# od1_redraw.net
KiCad netlist of a schematic drawn in EAGLE
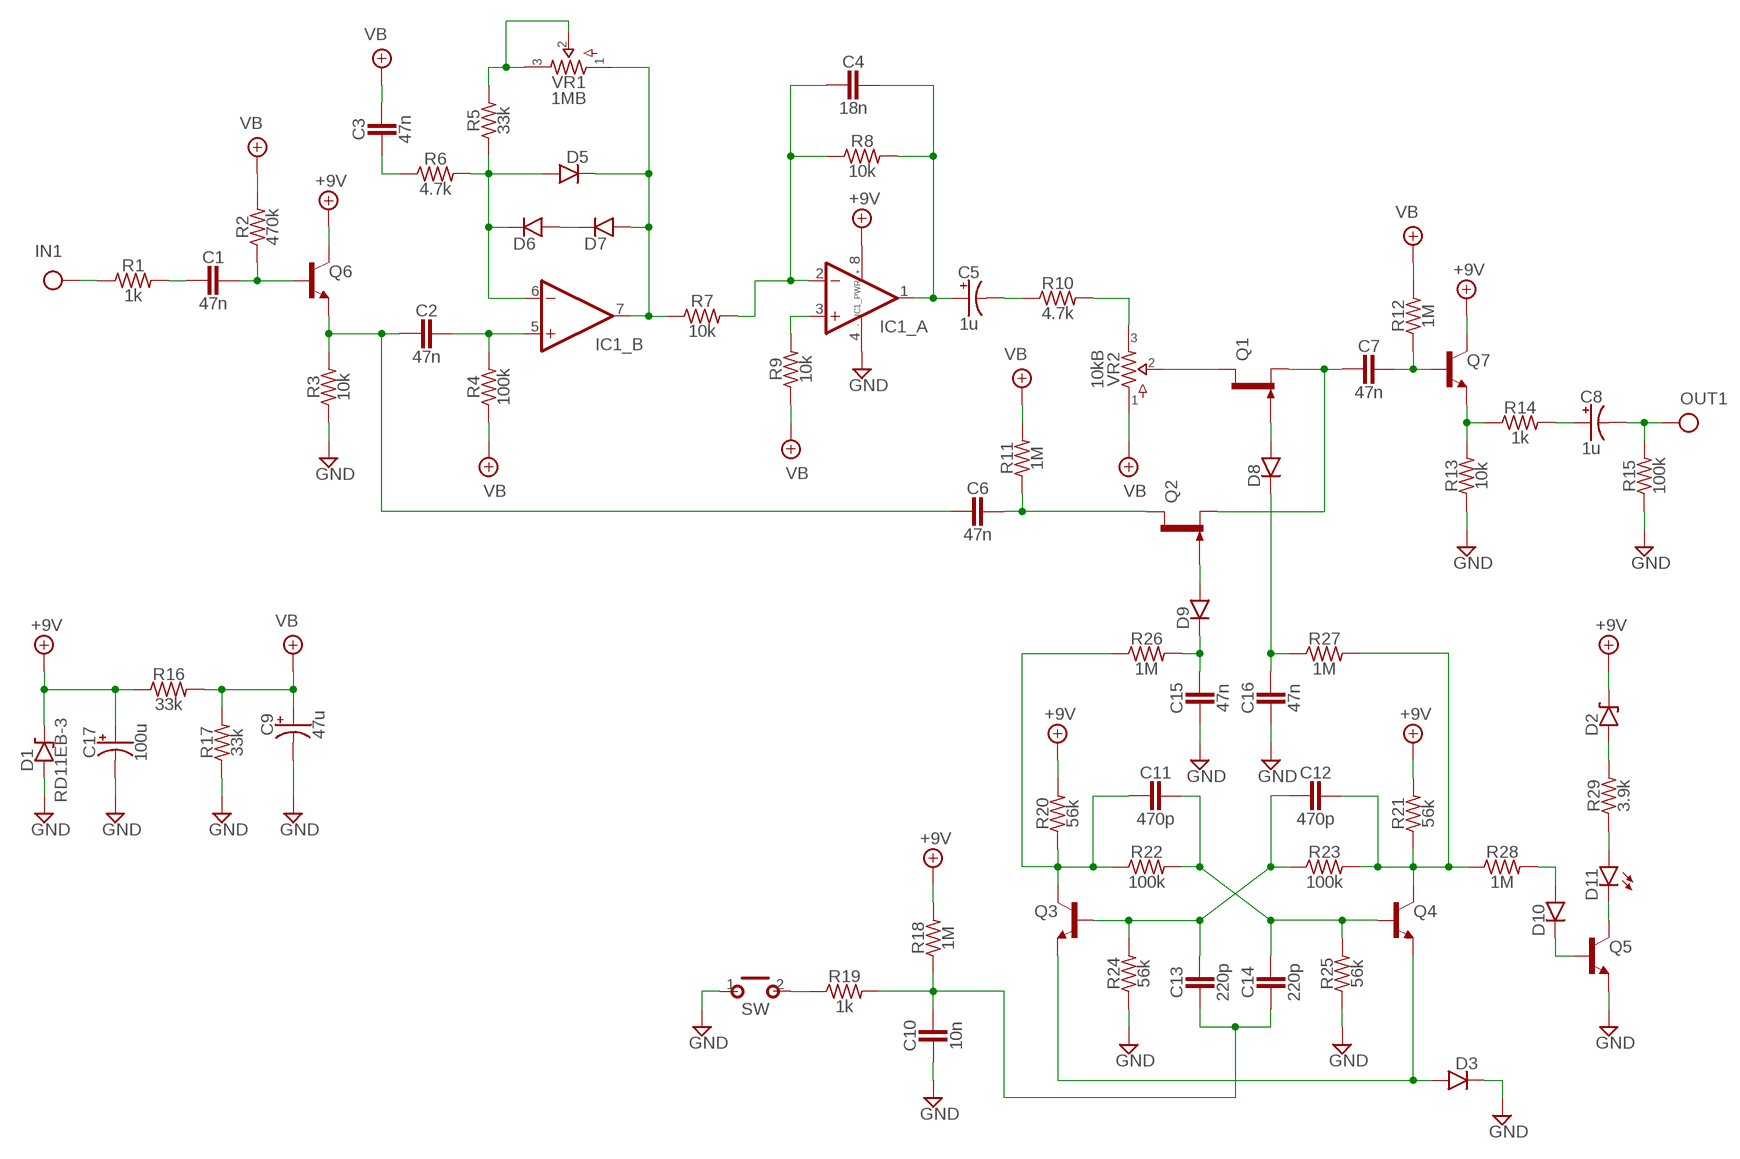
[diagram p0: schematic, sheet 1]

(export (version "E")
  (design (tool "Eeschema 10.0.6"))
  (components
    (comp (ref "C1")
      (value "47n")
      (footprint "eagle-import:BOX_SMALL")
      (libsource (lib "eagle-import") (part "CER/FILMBOX.1"))
    )
    (comp (ref "C2")
      (value "47n")
      (footprint "eagle-import:BOX_SMALL")
      (libsource (lib "eagle-import") (part "CER/FILMBOX.1"))
    )
    (comp (ref "C3")
      (value "47n")
      (footprint "eagle-import:BOX_SMALL")
      (libsource (lib "eagle-import") (part "CER/FILMBOX.1"))
    )
    (comp (ref "C4")
      (value "18n")
      (footprint "eagle-import:BOX_SMALL")
      (libsource (lib "eagle-import") (part "CER/FILMBOX.1"))
    )
    (comp (ref "C5")
      (value "1u")
      (footprint "eagle-import:040_020")
      (libsource (lib "eagle-import") (part "0400"))
    )
    (comp (ref "C6")
      (value "47n")
      (footprint "eagle-import:BOX_SMALL")
      (libsource (lib "eagle-import") (part "CER/FILMBOX.1"))
    )
    (comp (ref "C7")
      (value "47n")
      (footprint "eagle-import:BOX_SMALL")
      (libsource (lib "eagle-import") (part "CER/FILMBOX.1"))
    )
    (comp (ref "C8")
      (value "1u")
      (footprint "eagle-import:040_020")
      (libsource (lib "eagle-import") (part "0400"))
    )
    (comp (ref "C9")
      (value "47u")
      (footprint "eagle-import:040_020")
      (libsource (lib "eagle-import") (part "0400"))
    )
    (comp (ref "C10")
      (value "10n")
      (footprint "eagle-import:BOX_SMALL")
      (libsource (lib "eagle-import") (part "CER/FILMBOX.1"))
    )
    (comp (ref "C11")
      (value "470p")
      (footprint "eagle-import:BOX_SMALL")
      (libsource (lib "eagle-import") (part "CER/FILMBOX.1"))
    )
    (comp (ref "C12")
      (value "470p")
      (footprint "eagle-import:BOX_SMALL")
      (libsource (lib "eagle-import") (part "CER/FILMBOX.1"))
    )
    (comp (ref "C13")
      (value "220p")
      (footprint "eagle-import:BOX_SMALL")
      (libsource (lib "eagle-import") (part "CER/FILMBOX.1"))
    )
    (comp (ref "C14")
      (value "220p")
      (footprint "eagle-import:BOX_SMALL")
      (libsource (lib "eagle-import") (part "CER/FILMBOX.1"))
    )
    (comp (ref "C15")
      (value "47n")
      (footprint "eagle-import:BOX_SMALL")
      (libsource (lib "eagle-import") (part "CER/FILMBOX.1"))
    )
    (comp (ref "C16")
      (value "47n")
      (footprint "eagle-import:BOX_SMALL")
      (libsource (lib "eagle-import") (part "CER/FILMBOX.1"))
    )
    (comp (ref "C17")
      (value "100u")
      (footprint "eagle-import:040_020")
      (libsource (lib "eagle-import") (part "0400"))
    )
    (comp (ref "D1")
      (value "RD11EB-3")
      (footprint "eagle-import:DO41-2")
      (libsource (lib "eagle-import") (part "ZENER.2"))
    )
    (comp (ref "D2")
      (value "ZENER.2")
      (footprint "eagle-import:DO41-2")
      (libsource (lib "eagle-import") (part "ZENER.2"))
    )
    (comp (ref "D3")
      (value "DO35.2")
      (footprint "eagle-import:DO35-2")
      (libsource (lib "eagle-import") (part "DO35.2"))
    )
    (comp (ref "D5")
      (value "DO35.2")
      (footprint "eagle-import:DO35-2")
      (libsource (lib "eagle-import") (part "DO35.2"))
    )
    (comp (ref "D6")
      (value "DO35.2")
      (footprint "eagle-import:DO35-2")
      (libsource (lib "eagle-import") (part "DO35.2"))
    )
    (comp (ref "D7")
      (value "DO35.2")
      (footprint "eagle-import:DO35-2")
      (libsource (lib "eagle-import") (part "DO35.2"))
    )
    (comp (ref "D8")
      (value "DO35.2")
      (footprint "eagle-import:DO35-2")
      (libsource (lib "eagle-import") (part "DO35.2"))
    )
    (comp (ref "D9")
      (value "DO35.2")
      (footprint "eagle-import:DO35-2")
      (libsource (lib "eagle-import") (part "DO35.2"))
    )
    (comp (ref "D10")
      (value "DO35.2")
      (footprint "eagle-import:DO35-2")
      (libsource (lib "eagle-import") (part "DO35.2"))
    )
    (comp (ref "D11")
      (value "SLP1358")
      (footprint "eagle-import:3MM_D")
      (libsource (lib "eagle-import") (part "LED"))
    )
    (comp (ref "IC1")
      (value "DUALTH")
      (footprint "eagle-import:DIL0")
      (libsource (lib "eagle-import") (part "DUALTH"))
    )
    (comp (ref "Q1")
      (value "2N5457")
      (footprint "eagle-import:TO92-")
      (libsource (lib "eagle-import") (part "2N5457"))
    )
    (comp (ref "Q2")
      (value "2N5457")
      (footprint "eagle-import:TO92-")
      (libsource (lib "eagle-import") (part "2N5457"))
    )
    (comp (ref "Q3")
      (value "2SC828A")
      (footprint "eagle-import:TO92-")
      (libsource (lib "eagle-import") (part "2SC828A"))
    )
    (comp (ref "Q4")
      (value "2SC828A")
      (footprint "eagle-import:TO92-")
      (libsource (lib "eagle-import") (part "2SC828A"))
    )
    (comp (ref "Q5")
      (value "2SC828A")
      (footprint "eagle-import:TO92-")
      (libsource (lib "eagle-import") (part "2SC828A"))
    )
    (comp (ref "Q6")
      (value "2SC828A")
      (footprint "eagle-import:TO92-")
      (libsource (lib "eagle-import") (part "2SC828A"))
    )
    (comp (ref "Q7")
      (value "2SC828A")
      (footprint "eagle-import:TO92-")
      (libsource (lib "eagle-import") (part "2SC828A"))
    )
    (comp (ref "R1")
      (value "1k")
      (footprint "eagle-import:R0207_3")
      (libsource (lib "eagle-import") (part "R_.3B"))
    )
    (comp (ref "R2")
      (value "470k")
      (footprint "eagle-import:R0207_3")
      (libsource (lib "eagle-import") (part "R_.3B"))
    )
    (comp (ref "R3")
      (value "10k")
      (footprint "eagle-import:R0207_3")
      (libsource (lib "eagle-import") (part "R_.3B"))
    )
    (comp (ref "R4")
      (value "100k")
      (footprint "eagle-import:R0207_3")
      (libsource (lib "eagle-import") (part "R_.3B"))
    )
    (comp (ref "R5")
      (value "33k")
      (footprint "eagle-import:R0207_3")
      (libsource (lib "eagle-import") (part "R_.3B"))
    )
    (comp (ref "R6")
      (value "4.7k")
      (footprint "eagle-import:R0207_3")
      (libsource (lib "eagle-import") (part "R_.3B"))
    )
    (comp (ref "R7")
      (value "10k")
      (footprint "eagle-import:R0207_3")
      (libsource (lib "eagle-import") (part "R_.3B"))
    )
    (comp (ref "R8")
      (value "10k")
      (footprint "eagle-import:R0207_3")
      (libsource (lib "eagle-import") (part "R_.3B"))
    )
    (comp (ref "R9")
      (value "10k")
      (footprint "eagle-import:R0207_3")
      (libsource (lib "eagle-import") (part "R_.3B"))
    )
    (comp (ref "R10")
      (value "4.7k")
      (footprint "eagle-import:R0207_3")
      (libsource (lib "eagle-import") (part "R_.3B"))
    )
    (comp (ref "R11")
      (value "1M")
      (footprint "eagle-import:R0207_3")
      (libsource (lib "eagle-import") (part "R_.3B"))
    )
    (comp (ref "R12")
      (value "1M")
      (footprint "eagle-import:R0207_3")
      (libsource (lib "eagle-import") (part "R_.3B"))
    )
    (comp (ref "R13")
      (value "10k")
      (footprint "eagle-import:R0207_3")
      (libsource (lib "eagle-import") (part "R_.3B"))
    )
    (comp (ref "R14")
      (value "1k")
      (footprint "eagle-import:R0207_3")
      (libsource (lib "eagle-import") (part "R_.3B"))
    )
    (comp (ref "R15")
      (value "100k")
      (footprint "eagle-import:R0207_3")
      (libsource (lib "eagle-import") (part "R_.3B"))
    )
    (comp (ref "R16")
      (value "33k")
      (footprint "eagle-import:R0207_3")
      (libsource (lib "eagle-import") (part "R_.3B"))
    )
    (comp (ref "R17")
      (value "33k")
      (footprint "eagle-import:R0207_3")
      (libsource (lib "eagle-import") (part "R_.3B"))
    )
    (comp (ref "R18")
      (value "1M")
      (footprint "eagle-import:R0207_3")
      (libsource (lib "eagle-import") (part "R_.3B"))
    )
    (comp (ref "R19")
      (value "1k")
      (footprint "eagle-import:R0207_3")
      (libsource (lib "eagle-import") (part "R_.3B"))
    )
    (comp (ref "R20")
      (value "56k")
      (footprint "eagle-import:R0207_3")
      (libsource (lib "eagle-import") (part "R_.3B"))
    )
    (comp (ref "R21")
      (value "56k")
      (footprint "eagle-import:R0207_3")
      (libsource (lib "eagle-import") (part "R_.3B"))
    )
    (comp (ref "R22")
      (value "100k")
      (footprint "eagle-import:R0207_3")
      (libsource (lib "eagle-import") (part "R_.3B"))
    )
    (comp (ref "R23")
      (value "100k")
      (footprint "eagle-import:R0207_3")
      (libsource (lib "eagle-import") (part "R_.3B"))
    )
    (comp (ref "R24")
      (value "56k")
      (footprint "eagle-import:R0207_3")
      (libsource (lib "eagle-import") (part "R_.3B"))
    )
    (comp (ref "R25")
      (value "56k")
      (footprint "eagle-import:R0207_3")
      (libsource (lib "eagle-import") (part "R_.3B"))
    )
    (comp (ref "R26")
      (value "1M")
      (footprint "eagle-import:R0207_3")
      (libsource (lib "eagle-import") (part "R_.3B"))
    )
    (comp (ref "R27")
      (value "1M")
      (footprint "eagle-import:R0207_3")
      (libsource (lib "eagle-import") (part "R_.3B"))
    )
    (comp (ref "R28")
      (value "1M")
      (footprint "eagle-import:R0207_3")
      (libsource (lib "eagle-import") (part "R_.3B"))
    )
    (comp (ref "R29")
      (value "3.9k")
      (footprint "eagle-import:R0207_3")
      (libsource (lib "eagle-import") (part "R_.3B"))
    )
    (comp (ref "SW")
      (value "MOMENTARY")
      (footprint "eagle-import:SPST")
      (libsource (lib "eagle-import") (part "MOMENTARY"))
    )
    (comp (ref "VR1")
      (value "1MB")
      (footprint "eagle-import:16MM")
      (libsource (lib "eagle-import") (part "POTS16MM"))
    )
    (comp (ref "VR2")
      (value "10kB")
      (footprint "eagle-import:16MM")
      (libsource (lib "eagle-import") (part "POTS16MM"))
    )
  )
  (nets
    (net (code "1") (name "+9V") (class "Default")
      (node (ref "C17") (pin "+") (pinfunction "+_+") (pintype "passive"))
      (node (ref "D1") (pin "C") (pinfunction "C_C") (pintype "passive"))
      (node (ref "D2") (pin "C") (pinfunction "C_C") (pintype "passive"))
      (node (ref "IC1") (pin "8") (pinfunction "V+_8") (pintype "power_in"))
      (node (ref "Q6") (pin "2") (pinfunction "C_2") (pintype "passive"))
      (node (ref "Q7") (pin "2") (pinfunction "C_2") (pintype "passive"))
      (node (ref "R16") (pin "1") (pinfunction "1_1") (pintype "passive"))
      (node (ref "R18") (pin "2") (pinfunction "2_2") (pintype "passive"))
      (node (ref "R20") (pin "2") (pinfunction "2_2") (pintype "passive"))
      (node (ref "R21") (pin "2") (pinfunction "2_2") (pintype "passive"))
    )
    (net (code "2") (name "GND") (class "Default")
      (node (ref "C10") (pin "2") (pinfunction "2_2") (pintype "passive"))
      (node (ref "C15") (pin "2") (pinfunction "2_2") (pintype "passive"))
      (node (ref "C16") (pin "2") (pinfunction "2_2") (pintype "passive"))
      (node (ref "C17") (pin "-") (pinfunction "-_-") (pintype "passive"))
      (node (ref "C9") (pin "-") (pinfunction "-_-") (pintype "passive"))
      (node (ref "D1") (pin "A") (pinfunction "A_A") (pintype "passive"))
      (node (ref "D3") (pin "C") (pinfunction "C_C") (pintype "passive"))
      (node (ref "IC1") (pin "4") (pinfunction "V-_4") (pintype "power_in"))
      (node (ref "Q5") (pin "3") (pinfunction "E_3") (pintype "passive"))
      (node (ref "R13") (pin "1") (pinfunction "1_1") (pintype "passive"))
      (node (ref "R15") (pin "1") (pinfunction "1_1") (pintype "passive"))
      (node (ref "R17") (pin "1") (pinfunction "1_1") (pintype "passive"))
      (node (ref "R24") (pin "1") (pinfunction "1_1") (pintype "passive"))
      (node (ref "R25") (pin "1") (pinfunction "1_1") (pintype "passive"))
      (node (ref "R3") (pin "1") (pinfunction "1_1") (pintype "passive"))
      (node (ref "SW") (pin "1") (pinfunction "P_1") (pintype "passive"))
    )
    (net (code "3") (name "IN") (class "Default")
      (node (ref "R1") (pin "1") (pinfunction "1_1") (pintype "passive"))
    )
    (net (code "4") (name "Net-(C1-Pad2)") (class "Default")
      (node (ref "C1") (pin "2") (pinfunction "2_2") (pintype "passive"))
      (node (ref "R1") (pin "2") (pinfunction "2_2") (pintype "passive"))
    )
    (net (code "5") (name "Net-(C3-Pad2)") (class "Default")
      (node (ref "C3") (pin "2") (pinfunction "2_2") (pintype "passive"))
      (node (ref "R6") (pin "1") (pinfunction "1_1") (pintype "passive"))
    )
    (net (code "6") (name "Net-(C5-Pad-)") (class "Default")
      (node (ref "C5") (pin "-") (pinfunction "-_-") (pintype "passive"))
      (node (ref "R10") (pin "1") (pinfunction "1_1") (pintype "passive"))
    )
    (net (code "7") (name "Net-(C8-Pad+)") (class "Default")
      (node (ref "C8") (pin "+") (pinfunction "+_+") (pintype "passive"))
      (node (ref "R14") (pin "2") (pinfunction "2_2") (pintype "passive"))
    )
    (net (code "8") (name "Net-(C10-Pad1)") (class "Default")
      (node (ref "C10") (pin "1") (pinfunction "1_1") (pintype "passive"))
      (node (ref "C13") (pin "2") (pinfunction "2_2") (pintype "passive"))
      (node (ref "C14") (pin "2") (pinfunction "2_2") (pintype "passive"))
      (node (ref "R18") (pin "1") (pinfunction "1_1") (pintype "passive"))
      (node (ref "R19") (pin "2") (pinfunction "2_2") (pintype "passive"))
    )
    (net (code "9") (name "Net-(C15-Pad1)") (class "Default")
      (node (ref "C15") (pin "1") (pinfunction "1_1") (pintype "passive"))
      (node (ref "D9") (pin "C") (pinfunction "C_C") (pintype "passive"))
      (node (ref "R26") (pin "2") (pinfunction "2_2") (pintype "passive"))
    )
    (net (code "10") (name "Net-(C16-Pad1)") (class "Default")
      (node (ref "C16") (pin "1") (pinfunction "1_1") (pintype "passive"))
      (node (ref "D8") (pin "C") (pinfunction "C_C") (pintype "passive"))
      (node (ref "R27") (pin "1") (pinfunction "1_1") (pintype "passive"))
    )
    (net (code "11") (name "Net-(D2-PadA)") (class "Default")
      (node (ref "D2") (pin "A") (pinfunction "A_A") (pintype "passive"))
      (node (ref "R29") (pin "2") (pinfunction "2_2") (pintype "passive"))
    )
    (net (code "12") (name "Net-(D6-PadA)") (class "Default")
      (node (ref "D6") (pin "A") (pinfunction "A_A") (pintype "passive"))
      (node (ref "D7") (pin "C") (pinfunction "C_C") (pintype "passive"))
    )
    (net (code "13") (name "Net-(D10-PadA)") (class "Default")
      (node (ref "D10") (pin "A") (pinfunction "A_A") (pintype "passive"))
      (node (ref "R28") (pin "2") (pinfunction "2_2") (pintype "passive"))
    )
    (net (code "14") (name "Net-(D11-A)") (class "Default")
      (node (ref "D11") (pin "ANODE") (pinfunction "A_ANODE") (pintype "passive"))
      (node (ref "R29") (pin "1") (pinfunction "1_1") (pintype "passive"))
    )
    (net (code "15") (name "Net-(D11-C)") (class "Default")
      (node (ref "D11") (pin "P$1") (pinfunction "C_P$1") (pintype "passive"))
      (node (ref "Q5") (pin "2") (pinfunction "C_2") (pintype "passive"))
    )
    (net (code "16") (name "Net-(IC1A-+IN)") (class "Default")
      (node (ref "IC1") (pin "3") (pinfunction "+IN_3") (pintype "input"))
      (node (ref "R9") (pin "2") (pinfunction "2_2") (pintype "passive"))
    )
    (net (code "17") (name "Net-(IC1A--IN)") (class "Default")
      (node (ref "C4") (pin "2") (pinfunction "2_2") (pintype "passive"))
      (node (ref "IC1") (pin "2") (pinfunction "-IN_2") (pintype "input"))
      (node (ref "R7") (pin "2") (pinfunction "2_2") (pintype "passive"))
      (node (ref "R8") (pin "1") (pinfunction "1_1") (pintype "passive"))
    )
    (net (code "18") (name "Net-(IC1A-OUT)") (class "Default")
      (node (ref "C4") (pin "1") (pinfunction "1_1") (pintype "passive"))
      (node (ref "C5") (pin "+") (pinfunction "+_+") (pintype "passive"))
      (node (ref "IC1") (pin "1") (pinfunction "OUT_1") (pintype "output"))
      (node (ref "R8") (pin "2") (pinfunction "2_2") (pintype "passive"))
    )
    (net (code "19") (name "Net-(IC1B-+IN)") (class "Default")
      (node (ref "C2") (pin "1") (pinfunction "1_1") (pintype "passive"))
      (node (ref "IC1") (pin "5") (pinfunction "+IN_5") (pintype "input"))
      (node (ref "R4") (pin "2") (pinfunction "2_2") (pintype "passive"))
    )
    (net (code "20") (name "Net-(IC1B--IN)") (class "Default")
      (node (ref "D5") (pin "A") (pinfunction "A_A") (pintype "passive"))
      (node (ref "D6") (pin "C") (pinfunction "C_C") (pintype "passive"))
      (node (ref "IC1") (pin "6") (pinfunction "-IN_6") (pintype "input"))
      (node (ref "R5") (pin "1") (pinfunction "1_1") (pintype "passive"))
      (node (ref "R6") (pin "2") (pinfunction "2_2") (pintype "passive"))
    )
    (net (code "21") (name "Net-(IC1B-OUT)") (class "Default")
      (node (ref "D5") (pin "C") (pinfunction "C_C") (pintype "passive"))
      (node (ref "D7") (pin "A") (pinfunction "A_A") (pintype "passive"))
      (node (ref "IC1") (pin "7") (pinfunction "OUT_7") (pintype "output"))
      (node (ref "R7") (pin "1") (pinfunction "1_1") (pintype "passive"))
      (node (ref "VR1") (pin "1") (pinfunction "1_1") (pintype "passive"))
    )
    (net (code "22") (name "Net-(Q1-D)") (class "Default")
      (node (ref "Q1") (pin "3") (pinfunction "D_3") (pintype "passive"))
      (node (ref "VR2") (pin "2") (pinfunction "2_2") (pintype "passive"))
    )
    (net (code "23") (name "Net-(Q1-G)") (class "Default")
      (node (ref "D8") (pin "A") (pinfunction "A_A") (pintype "passive"))
      (node (ref "Q1") (pin "1") (pinfunction "G_1") (pintype "passive"))
    )
    (net (code "24") (name "Net-(Q1-S)") (class "Default")
      (node (ref "C7") (pin "2") (pinfunction "2_2") (pintype "passive"))
      (node (ref "Q1") (pin "2") (pinfunction "S_2") (pintype "passive"))
      (node (ref "Q2") (pin "2") (pinfunction "S_2") (pintype "passive"))
    )
    (net (code "25") (name "Net-(Q2-D)") (class "Default")
      (node (ref "C6") (pin "1") (pinfunction "1_1") (pintype "passive"))
      (node (ref "Q2") (pin "3") (pinfunction "D_3") (pintype "passive"))
      (node (ref "R11") (pin "1") (pinfunction "1_1") (pintype "passive"))
    )
    (net (code "26") (name "Net-(Q2-G)") (class "Default")
      (node (ref "D9") (pin "A") (pinfunction "A_A") (pintype "passive"))
      (node (ref "Q2") (pin "1") (pinfunction "G_1") (pintype "passive"))
    )
    (net (code "27") (name "Net-(Q3-B)") (class "Default")
      (node (ref "C12") (pin "2") (pinfunction "2_2") (pintype "passive"))
      (node (ref "C13") (pin "1") (pinfunction "1_1") (pintype "passive"))
      (node (ref "Q3") (pin "1") (pinfunction "B_1") (pintype "passive"))
      (node (ref "R23") (pin "1") (pinfunction "1_1") (pintype "passive"))
      (node (ref "R24") (pin "2") (pinfunction "2_2") (pintype "passive"))
    )
    (net (code "28") (name "Net-(Q3-C)") (class "Default")
      (node (ref "C11") (pin "2") (pinfunction "2_2") (pintype "passive"))
      (node (ref "Q3") (pin "2") (pinfunction "C_2") (pintype "passive"))
      (node (ref "R20") (pin "1") (pinfunction "1_1") (pintype "passive"))
      (node (ref "R22") (pin "1") (pinfunction "1_1") (pintype "passive"))
      (node (ref "R26") (pin "1") (pinfunction "1_1") (pintype "passive"))
    )
    (net (code "29") (name "Net-(Q3-E)") (class "Default")
      (node (ref "D3") (pin "A") (pinfunction "A_A") (pintype "passive"))
      (node (ref "Q3") (pin "3") (pinfunction "E_3") (pintype "passive"))
      (node (ref "Q4") (pin "3") (pinfunction "E_3") (pintype "passive"))
    )
    (net (code "30") (name "Net-(Q4-B)") (class "Default")
      (node (ref "C11") (pin "1") (pinfunction "1_1") (pintype "passive"))
      (node (ref "C14") (pin "1") (pinfunction "1_1") (pintype "passive"))
      (node (ref "Q4") (pin "1") (pinfunction "B_1") (pintype "passive"))
      (node (ref "R22") (pin "2") (pinfunction "2_2") (pintype "passive"))
      (node (ref "R25") (pin "2") (pinfunction "2_2") (pintype "passive"))
    )
    (net (code "31") (name "Net-(Q4-C)") (class "Default")
      (node (ref "C12") (pin "1") (pinfunction "1_1") (pintype "passive"))
      (node (ref "Q4") (pin "2") (pinfunction "C_2") (pintype "passive"))
      (node (ref "R21") (pin "1") (pinfunction "1_1") (pintype "passive"))
      (node (ref "R23") (pin "2") (pinfunction "2_2") (pintype "passive"))
      (node (ref "R27") (pin "2") (pinfunction "2_2") (pintype "passive"))
      (node (ref "R28") (pin "1") (pinfunction "1_1") (pintype "passive"))
    )
    (net (code "32") (name "Net-(Q5-B)") (class "Default")
      (node (ref "D10") (pin "C") (pinfunction "C_C") (pintype "passive"))
      (node (ref "Q5") (pin "1") (pinfunction "B_1") (pintype "passive"))
    )
    (net (code "33") (name "Net-(Q6-B)") (class "Default")
      (node (ref "C1") (pin "1") (pinfunction "1_1") (pintype "passive"))
      (node (ref "Q6") (pin "1") (pinfunction "B_1") (pintype "passive"))
      (node (ref "R2") (pin "1") (pinfunction "1_1") (pintype "passive"))
    )
    (net (code "34") (name "Net-(Q6-E)") (class "Default")
      (node (ref "C2") (pin "2") (pinfunction "2_2") (pintype "passive"))
      (node (ref "C6") (pin "2") (pinfunction "2_2") (pintype "passive"))
      (node (ref "Q6") (pin "3") (pinfunction "E_3") (pintype "passive"))
      (node (ref "R3") (pin "2") (pinfunction "2_2") (pintype "passive"))
    )
    (net (code "35") (name "Net-(Q7-B)") (class "Default")
      (node (ref "C7") (pin "1") (pinfunction "1_1") (pintype "passive"))
      (node (ref "Q7") (pin "1") (pinfunction "B_1") (pintype "passive"))
      (node (ref "R12") (pin "1") (pinfunction "1_1") (pintype "passive"))
    )
    (net (code "36") (name "Net-(Q7-E)") (class "Default")
      (node (ref "Q7") (pin "3") (pinfunction "E_3") (pintype "passive"))
      (node (ref "R13") (pin "2") (pinfunction "2_2") (pintype "passive"))
      (node (ref "R14") (pin "1") (pinfunction "1_1") (pintype "passive"))
    )
    (net (code "37") (name "Net-(R5-Pad2)") (class "Default")
      (node (ref "R5") (pin "2") (pinfunction "2_2") (pintype "passive"))
      (node (ref "VR1") (pin "2") (pinfunction "2_2") (pintype "passive"))
      (node (ref "VR1") (pin "3") (pinfunction "3_3") (pintype "passive"))
    )
    (net (code "38") (name "Net-(R10-Pad2)") (class "Default")
      (node (ref "R10") (pin "2") (pinfunction "2_2") (pintype "passive"))
      (node (ref "VR2") (pin "3") (pinfunction "3_3") (pintype "passive"))
    )
    (net (code "39") (name "Net-(SW-S)") (class "Default")
      (node (ref "R19") (pin "1") (pinfunction "1_1") (pintype "passive"))
      (node (ref "SW") (pin "2") (pinfunction "S_2") (pintype "passive"))
    )
    (net (code "40") (name "OUT") (class "Default")
      (node (ref "C8") (pin "-") (pinfunction "-_-") (pintype "passive"))
      (node (ref "R15") (pin "2") (pinfunction "2_2") (pintype "passive"))
    )
    (net (code "41") (name "VB") (class "Default")
      (node (ref "C3") (pin "1") (pinfunction "1_1") (pintype "passive"))
      (node (ref "C9") (pin "+") (pinfunction "+_+") (pintype "passive"))
      (node (ref "R11") (pin "2") (pinfunction "2_2") (pintype "passive"))
      (node (ref "R12") (pin "2") (pinfunction "2_2") (pintype "passive"))
      (node (ref "R16") (pin "2") (pinfunction "2_2") (pintype "passive"))
      (node (ref "R17") (pin "2") (pinfunction "2_2") (pintype "passive"))
      (node (ref "R2") (pin "2") (pinfunction "2_2") (pintype "passive"))
      (node (ref "R4") (pin "1") (pinfunction "1_1") (pintype "passive"))
      (node (ref "R9") (pin "1") (pinfunction "1_1") (pintype "passive"))
      (node (ref "VR2") (pin "1") (pinfunction "1_1") (pintype "passive"))
    )
  )
)
